# MB_RELAY.net
KiCad netlist of a schematic drawn in Altium Designer
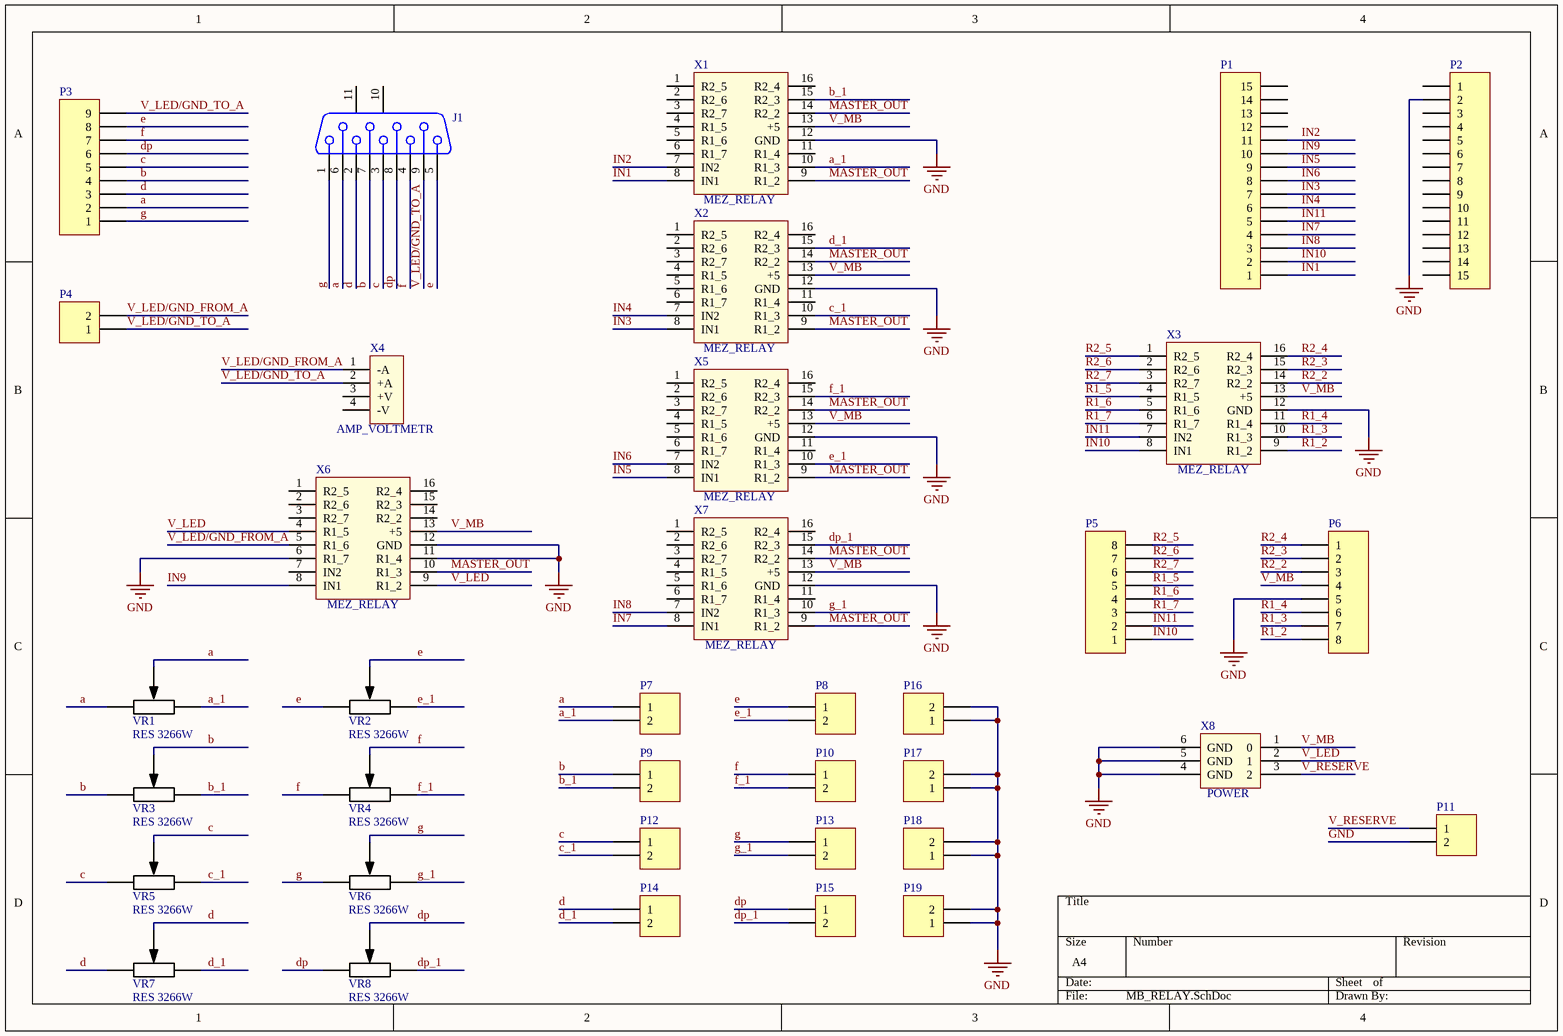
[diagram p0: MB_RELAY.SchDoc]

(export (version "E")
  (design (tool "Eeschema 10.0.6"))
  (components
    (comp (ref "J1")
      (value "D Connector 9")
      (footprint "DSUB1.385-2H9")
      (description "Receptacle Assembly, 9 Position, Right Angle")
      (fields (field (name "PUBLISHER") "Altium Limited"))
      (libsource (lib "Miscellaneous Connectors") (part "D Connector 9"))
    )
    (comp (ref "P1")
      (value "Header 15")
      (footprint "HDR1X15")
      (description "Header, 15-Pin")
      (fields (field (name "PUBLISHER") "Altium Limited"))
      (libsource (lib "Miscellaneous Connectors") (part "Header 15"))
    )
    (comp (ref "P2")
      (value "Header 15")
      (footprint "HDR1X15")
      (description "Header, 15-Pin")
      (fields (field (name "PUBLISHER") "Altium Limited"))
      (libsource (lib "") (part "Header 15_1"))
    )
    (comp (ref "P3")
      (value "Header 9")
      (footprint "HDR1X9")
      (description "Header, 9-Pin")
      (fields (field (name "PUBLISHER") "Altium Limited"))
      (libsource (lib "Miscellaneous Connectors") (part "Header 9"))
    )
    (comp (ref "P4")
      (value "Header 2")
      (footprint "HDR1X2")
      (description "Header, 2-Pin")
      (fields (field (name "PUBLISHER") "Altium Limited"))
      (libsource (lib "Miscellaneous Connectors") (part "Header 2"))
    )
    (comp (ref "P5")
      (value "Header 8")
      (footprint "HDR1X8")
      (description "Header, 8-Pin")
      (fields (field (name "PUBLISHER") "Altium Limited"))
      (libsource (lib "Miscellaneous Connectors") (part "Header 8"))
    )
    (comp (ref "P6")
      (value "Header 8")
      (footprint "HDR1X8")
      (description "Header, 8-Pin")
      (fields (field (name "PUBLISHER") "Altium Limited"))
      (libsource (lib "") (part "Header 8_1"))
    )
    (comp (ref "P7")
      (value "Header 2")
      (footprint "HDR1X2")
      (description "Header, 2-Pin")
      (fields (field (name "PUBLISHER") "Altium Limited"))
      (libsource (lib "") (part "Header 2_1"))
    )
    (comp (ref "P8")
      (value "Header 2")
      (footprint "HDR1X2")
      (description "Header, 2-Pin")
      (fields (field (name "PUBLISHER") "Altium Limited"))
      (libsource (lib "") (part "Header 2_1"))
    )
    (comp (ref "P9")
      (value "Header 2")
      (footprint "HDR1X2")
      (description "Header, 2-Pin")
      (fields (field (name "PUBLISHER") "Altium Limited"))
      (libsource (lib "") (part "Header 2_1"))
    )
    (comp (ref "P10")
      (value "Header 2")
      (footprint "HDR1X2")
      (description "Header, 2-Pin")
      (fields (field (name "PUBLISHER") "Altium Limited"))
      (libsource (lib "") (part "Header 2_1"))
    )
    (comp (ref "P11")
      (value "Header 2")
      (footprint "HDR1X2")
      (description "Header, 2-Pin")
      (fields (field (name "PUBLISHER") "Altium Limited"))
      (libsource (lib "") (part "Header 2_1"))
    )
    (comp (ref "P12")
      (value "Header 2")
      (footprint "HDR1X2")
      (description "Header, 2-Pin")
      (fields (field (name "PUBLISHER") "Altium Limited"))
      (libsource (lib "") (part "Header 2_1"))
    )
    (comp (ref "P13")
      (value "Header 2")
      (footprint "HDR1X2")
      (description "Header, 2-Pin")
      (fields (field (name "PUBLISHER") "Altium Limited"))
      (libsource (lib "") (part "Header 2_1"))
    )
    (comp (ref "P14")
      (value "Header 2")
      (footprint "HDR1X2")
      (description "Header, 2-Pin")
      (fields (field (name "PUBLISHER") "Altium Limited"))
      (libsource (lib "") (part "Header 2_1"))
    )
    (comp (ref "P15")
      (value "Header 2")
      (footprint "HDR1X2")
      (description "Header, 2-Pin")
      (fields (field (name "PUBLISHER") "Altium Limited"))
      (libsource (lib "") (part "Header 2_1"))
    )
    (comp (ref "P16")
      (value "Header 2")
      (footprint "HDR1X2")
      (description "Header, 2-Pin")
      (fields (field (name "PUBLISHER") "Altium Limited"))
      (libsource (lib "Miscellaneous Connectors") (part "Header 2"))
    )
    (comp (ref "P17")
      (value "Header 2")
      (footprint "HDR1X2")
      (description "Header, 2-Pin")
      (fields (field (name "PUBLISHER") "Altium Limited"))
      (libsource (lib "Miscellaneous Connectors") (part "Header 2"))
    )
    (comp (ref "P18")
      (value "Header 2")
      (footprint "HDR1X2")
      (description "Header, 2-Pin")
      (fields (field (name "PUBLISHER") "Altium Limited"))
      (libsource (lib "Miscellaneous Connectors") (part "Header 2"))
    )
    (comp (ref "P19")
      (value "Header 2")
      (footprint "HDR1X2")
      (description "Header, 2-Pin")
      (fields (field (name "PUBLISHER") "Altium Limited"))
      (libsource (lib "Miscellaneous Connectors") (part "Header 2"))
    )
    (comp (ref "VR1")
      (value "RES 3266W")
      (footprint "aab_Passive:RES 3266W")
      (libsource (lib "aab_Schlib") (part "RES 3266W"))
    )
    (comp (ref "VR2")
      (value "RES 3266W")
      (footprint "aab_Passive:RES 3266W")
      (libsource (lib "aab_Schlib") (part "RES 3266W"))
    )
    (comp (ref "VR3")
      (value "RES 3266W")
      (footprint "aab_Passive:RES 3266W")
      (libsource (lib "aab_Schlib") (part "RES 3266W"))
    )
    (comp (ref "VR4")
      (value "RES 3266W")
      (footprint "aab_Passive:RES 3266W")
      (libsource (lib "aab_Schlib") (part "RES 3266W"))
    )
    (comp (ref "VR5")
      (value "RES 3266W")
      (footprint "aab_Passive:RES 3266W")
      (libsource (lib "aab_Schlib") (part "RES 3266W"))
    )
    (comp (ref "VR6")
      (value "RES 3266W")
      (footprint "aab_Passive:RES 3266W")
      (libsource (lib "aab_Schlib") (part "RES 3266W"))
    )
    (comp (ref "VR7")
      (value "RES 3266W")
      (footprint "aab_Passive:RES 3266W")
      (libsource (lib "aab_Schlib") (part "RES 3266W"))
    )
    (comp (ref "VR8")
      (value "RES 3266W")
      (footprint "aab_Passive:RES 3266W")
      (libsource (lib "aab_Schlib") (part "RES 3266W"))
    )
    (comp (ref "X1")
      (value "MEZ_RELAY")
      (footprint "MEZ_RELAY")
      (libsource (lib "msp_SchLib") (part "MEZ_RELAY"))
    )
    (comp (ref "X2")
      (value "MEZ_RELAY")
      (footprint "MEZ_RELAY")
      (libsource (lib "msp_SchLib") (part "MEZ_RELAY"))
    )
    (comp (ref "X3")
      (value "MEZ_RELAY")
      (footprint "MEZ_RELAY")
      (libsource (lib "msp_SchLib") (part "MEZ_RELAY"))
    )
    (comp (ref "X4")
      (value "AMP_VOLTMETR")
      (footprint "vpl_Passive:AMP_VOLTMETER")
      (libsource (lib "msp_SchLib") (part "AMP_VOLTMETR"))
    )
    (comp (ref "X5")
      (value "MEZ_RELAY")
      (footprint "MEZ_RELAY")
      (libsource (lib "msp_SchLib") (part "MEZ_RELAY"))
    )
    (comp (ref "X6")
      (value "MEZ_RELAY")
      (footprint "MEZ_RELAY")
      (libsource (lib "msp_SchLib") (part "MEZ_RELAY"))
    )
    (comp (ref "X7")
      (value "MEZ_RELAY")
      (footprint "MEZ_RELAY")
      (libsource (lib "msp_SchLib") (part "MEZ_RELAY"))
    )
    (comp (ref "X8")
      (value "POWER")
      (footprint "vpl_Passive:POWER")
      (libsource (lib "msp_SchLib") (part "POWER"))
    )
  )
  (nets
    (net (code "1") (name "/IN1") (class "Default")
      (node (ref "P1") (pin "1") (pinfunction "1_1") (pintype "passive"))
      (node (ref "X1") (pin "8") (pinfunction "IN1_8") (pintype "passive"))
    )
    (net (code "2") (name "/IN2") (class "Default")
      (node (ref "P1") (pin "11") (pinfunction "11_11") (pintype "passive"))
      (node (ref "X1") (pin "7") (pinfunction "IN2_7") (pintype "passive"))
    )
    (net (code "3") (name "/IN3") (class "Default")
      (node (ref "P1") (pin "7") (pinfunction "7_7") (pintype "passive"))
      (node (ref "X2") (pin "8") (pinfunction "IN1_8") (pintype "passive"))
    )
    (net (code "4") (name "/IN4") (class "Default")
      (node (ref "P1") (pin "6") (pinfunction "6_6") (pintype "passive"))
      (node (ref "X2") (pin "7") (pinfunction "IN2_7") (pintype "passive"))
    )
    (net (code "5") (name "/IN5") (class "Default")
      (node (ref "P1") (pin "9") (pinfunction "9_9") (pintype "passive"))
      (node (ref "X5") (pin "8") (pinfunction "IN1_8") (pintype "passive"))
    )
    (net (code "6") (name "/IN6") (class "Default")
      (node (ref "P1") (pin "8") (pinfunction "8_8") (pintype "passive"))
      (node (ref "X5") (pin "7") (pinfunction "IN2_7") (pintype "passive"))
    )
    (net (code "7") (name "/IN7") (class "Default")
      (node (ref "P1") (pin "4") (pinfunction "4_4") (pintype "passive"))
      (node (ref "X7") (pin "8") (pinfunction "IN1_8") (pintype "passive"))
    )
    (net (code "8") (name "/IN8") (class "Default")
      (node (ref "P1") (pin "3") (pinfunction "3_3") (pintype "passive"))
      (node (ref "X7") (pin "7") (pinfunction "IN2_7") (pintype "passive"))
    )
    (net (code "9") (name "/IN9") (class "Default")
      (node (ref "P1") (pin "10") (pinfunction "10_10") (pintype "passive"))
      (node (ref "X6") (pin "8") (pinfunction "IN1_8") (pintype "passive"))
    )
    (net (code "10") (name "/IN10") (class "Default")
      (node (ref "P1") (pin "2") (pinfunction "2_2") (pintype "passive"))
      (node (ref "P5") (pin "1") (pinfunction "1_1") (pintype "passive"))
      (node (ref "X3") (pin "8") (pinfunction "IN1_8") (pintype "passive"))
    )
    (net (code "11") (name "/IN11") (class "Default")
      (node (ref "P1") (pin "5") (pinfunction "5_5") (pintype "passive"))
      (node (ref "P5") (pin "2") (pinfunction "2_2") (pintype "passive"))
      (node (ref "X3") (pin "7") (pinfunction "IN2_7") (pintype "passive"))
    )
    (net (code "12") (name "/MASTER_OUT") (class "Default")
      (node (ref "X1") (pin "14") (pinfunction "R2_2_14") (pintype "passive"))
      (node (ref "X1") (pin "9") (pinfunction "R1_2_9") (pintype "passive"))
      (node (ref "X2") (pin "14") (pinfunction "R2_2_14") (pintype "passive"))
      (node (ref "X2") (pin "9") (pinfunction "R1_2_9") (pintype "passive"))
      (node (ref "X5") (pin "14") (pinfunction "R2_2_14") (pintype "passive"))
      (node (ref "X5") (pin "9") (pinfunction "R1_2_9") (pintype "passive"))
      (node (ref "X6") (pin "10") (pinfunction "R1_3_10") (pintype "passive"))
      (node (ref "X7") (pin "14") (pinfunction "R2_2_14") (pintype "passive"))
      (node (ref "X7") (pin "9") (pinfunction "R1_2_9") (pintype "passive"))
    )
    (net (code "13") (name "/R1_2") (class "Default")
      (node (ref "P6") (pin "8") (pinfunction "8_8") (pintype "passive"))
      (node (ref "X3") (pin "9") (pinfunction "R1_2_9") (pintype "passive"))
    )
    (net (code "14") (name "/R1_3") (class "Default")
      (node (ref "P6") (pin "7") (pinfunction "7_7") (pintype "passive"))
      (node (ref "X3") (pin "10") (pinfunction "R1_3_10") (pintype "passive"))
    )
    (net (code "15") (name "/R1_4") (class "Default")
      (node (ref "P6") (pin "6") (pinfunction "6_6") (pintype "passive"))
      (node (ref "X3") (pin "11") (pinfunction "R1_4_11") (pintype "passive"))
    )
    (net (code "16") (name "/R1_5") (class "Default")
      (node (ref "P5") (pin "5") (pinfunction "5_5") (pintype "passive"))
      (node (ref "X3") (pin "4") (pinfunction "R1_5_4") (pintype "passive"))
    )
    (net (code "17") (name "/R1_6") (class "Default")
      (node (ref "P5") (pin "4") (pinfunction "4_4") (pintype "passive"))
      (node (ref "X3") (pin "5") (pinfunction "R1_6_5") (pintype "passive"))
    )
    (net (code "18") (name "/R1_7") (class "Default")
      (node (ref "P5") (pin "3") (pinfunction "3_3") (pintype "passive"))
      (node (ref "X3") (pin "6") (pinfunction "R1_7_6") (pintype "passive"))
    )
    (net (code "19") (name "/R2_2") (class "Default")
      (node (ref "P6") (pin "3") (pinfunction "3_3") (pintype "passive"))
      (node (ref "X3") (pin "14") (pinfunction "R2_2_14") (pintype "passive"))
    )
    (net (code "20") (name "/R2_3") (class "Default")
      (node (ref "P6") (pin "2") (pinfunction "2_2") (pintype "passive"))
      (node (ref "X3") (pin "15") (pinfunction "R2_3_15") (pintype "passive"))
    )
    (net (code "21") (name "/R2_4") (class "Default")
      (node (ref "P6") (pin "1") (pinfunction "1_1") (pintype "passive"))
      (node (ref "X3") (pin "16") (pinfunction "R2_4_16") (pintype "passive"))
    )
    (net (code "22") (name "/R2_5") (class "Default")
      (node (ref "P5") (pin "8") (pinfunction "8_8") (pintype "passive"))
      (node (ref "X3") (pin "1") (pinfunction "R2_5_1") (pintype "passive"))
    )
    (net (code "23") (name "/R2_6") (class "Default")
      (node (ref "P5") (pin "7") (pinfunction "7_7") (pintype "passive"))
      (node (ref "X3") (pin "2") (pinfunction "R2_6_2") (pintype "passive"))
    )
    (net (code "24") (name "/R2_7") (class "Default")
      (node (ref "P5") (pin "6") (pinfunction "6_6") (pintype "passive"))
      (node (ref "X3") (pin "3") (pinfunction "R2_7_3") (pintype "passive"))
    )
    (net (code "25") (name "/V_LED") (class "Default")
      (node (ref "X6") (pin "4") (pinfunction "R1_5_4") (pintype "passive"))
      (node (ref "X6") (pin "9") (pinfunction "R1_2_9") (pintype "passive"))
      (node (ref "X8") (pin "2") (pinfunction "1_2") (pintype "passive"))
    )
    (net (code "26") (name "/V_LED{slash}GND_FROM_A") (class "Default")
      (node (ref "P4") (pin "2") (pinfunction "2_2") (pintype "passive"))
      (node (ref "X4") (pin "1") (pinfunction "-A_1") (pintype "passive"))
      (node (ref "X6") (pin "5") (pinfunction "R1_6_5") (pintype "passive"))
    )
    (net (code "27") (name "/V_LED{slash}GND_TO_A") (class "Default")
      (node (ref "J1") (pin "9") (pinfunction "9_9") (pintype "passive"))
      (node (ref "P3") (pin "9") (pinfunction "9_9") (pintype "passive"))
      (node (ref "P4") (pin "1") (pinfunction "1_1") (pintype "passive"))
      (node (ref "X4") (pin "2") (pinfunction "+A_2") (pintype "passive"))
    )
    (net (code "28") (name "/V_MB") (class "Default")
      (node (ref "P6") (pin "4") (pinfunction "4_4") (pintype "passive"))
      (node (ref "X1") (pin "13") (pinfunction "+5_13") (pintype "passive"))
      (node (ref "X2") (pin "13") (pinfunction "+5_13") (pintype "passive"))
      (node (ref "X3") (pin "13") (pinfunction "+5_13") (pintype "passive"))
      (node (ref "X5") (pin "13") (pinfunction "+5_13") (pintype "passive"))
      (node (ref "X6") (pin "13") (pinfunction "+5_13") (pintype "passive"))
      (node (ref "X7") (pin "13") (pinfunction "+5_13") (pintype "passive"))
      (node (ref "X8") (pin "1") (pinfunction "0_1") (pintype "passive"))
    )
    (net (code "29") (name "/V_RESERVE") (class "Default")
      (node (ref "P11") (pin "1") (pinfunction "1_1") (pintype "passive"))
      (node (ref "X8") (pin "3") (pinfunction "2_3") (pintype "passive"))
    )
    (net (code "30") (name "/a") (class "Default")
      (node (ref "J1") (pin "6") (pinfunction "6_6") (pintype "passive"))
      (node (ref "P3") (pin "2") (pinfunction "2_2") (pintype "passive"))
      (node (ref "P7") (pin "1") (pinfunction "1_1") (pintype "passive"))
      (node (ref "VR1") (pin "1") (pinfunction "1_1") (pintype "passive"))
      (node (ref "VR1") (pin "2") (pinfunction "2_2") (pintype "passive"))
    )
    (net (code "31") (name "/a_1") (class "Default")
      (node (ref "P7") (pin "2") (pinfunction "2_2") (pintype "passive"))
      (node (ref "VR1") (pin "3") (pinfunction "3_3") (pintype "passive"))
      (node (ref "X1") (pin "10") (pinfunction "R1_3_10") (pintype "passive"))
    )
    (net (code "32") (name "/b") (class "Default")
      (node (ref "J1") (pin "7") (pinfunction "7_7") (pintype "passive"))
      (node (ref "P3") (pin "4") (pinfunction "4_4") (pintype "passive"))
      (node (ref "P9") (pin "1") (pinfunction "1_1") (pintype "passive"))
      (node (ref "VR3") (pin "1") (pinfunction "1_1") (pintype "passive"))
      (node (ref "VR3") (pin "2") (pinfunction "2_2") (pintype "passive"))
    )
    (net (code "33") (name "/b_1") (class "Default")
      (node (ref "P9") (pin "2") (pinfunction "2_2") (pintype "passive"))
      (node (ref "VR3") (pin "3") (pinfunction "3_3") (pintype "passive"))
      (node (ref "X1") (pin "15") (pinfunction "R2_3_15") (pintype "passive"))
    )
    (net (code "34") (name "/c") (class "Default")
      (node (ref "J1") (pin "3") (pinfunction "3_3") (pintype "passive"))
      (node (ref "P12") (pin "1") (pinfunction "1_1") (pintype "passive"))
      (node (ref "P3") (pin "5") (pinfunction "5_5") (pintype "passive"))
      (node (ref "VR5") (pin "1") (pinfunction "1_1") (pintype "passive"))
      (node (ref "VR5") (pin "2") (pinfunction "2_2") (pintype "passive"))
    )
    (net (code "35") (name "/c_1") (class "Default")
      (node (ref "P12") (pin "2") (pinfunction "2_2") (pintype "passive"))
      (node (ref "VR5") (pin "3") (pinfunction "3_3") (pintype "passive"))
      (node (ref "X2") (pin "10") (pinfunction "R1_3_10") (pintype "passive"))
    )
    (net (code "36") (name "/d") (class "Default")
      (node (ref "J1") (pin "2") (pinfunction "2_2") (pintype "passive"))
      (node (ref "P14") (pin "1") (pinfunction "1_1") (pintype "passive"))
      (node (ref "P3") (pin "3") (pinfunction "3_3") (pintype "passive"))
      (node (ref "VR7") (pin "1") (pinfunction "1_1") (pintype "passive"))
      (node (ref "VR7") (pin "2") (pinfunction "2_2") (pintype "passive"))
    )
    (net (code "37") (name "/d_1") (class "Default")
      (node (ref "P14") (pin "2") (pinfunction "2_2") (pintype "passive"))
      (node (ref "VR7") (pin "3") (pinfunction "3_3") (pintype "passive"))
      (node (ref "X2") (pin "15") (pinfunction "R2_3_15") (pintype "passive"))
    )
    (net (code "38") (name "/dp") (class "Default")
      (node (ref "J1") (pin "8") (pinfunction "8_8") (pintype "passive"))
      (node (ref "P15") (pin "1") (pinfunction "1_1") (pintype "passive"))
      (node (ref "P3") (pin "6") (pinfunction "6_6") (pintype "passive"))
      (node (ref "VR8") (pin "1") (pinfunction "1_1") (pintype "passive"))
      (node (ref "VR8") (pin "2") (pinfunction "2_2") (pintype "passive"))
    )
    (net (code "39") (name "/dp_1") (class "Default")
      (node (ref "P15") (pin "2") (pinfunction "2_2") (pintype "passive"))
      (node (ref "VR8") (pin "3") (pinfunction "3_3") (pintype "passive"))
      (node (ref "X7") (pin "15") (pinfunction "R2_3_15") (pintype "passive"))
    )
    (net (code "40") (name "/e") (class "Default")
      (node (ref "J1") (pin "5") (pinfunction "5_5") (pintype "passive"))
      (node (ref "P3") (pin "8") (pinfunction "8_8") (pintype "passive"))
      (node (ref "P8") (pin "1") (pinfunction "1_1") (pintype "passive"))
      (node (ref "VR2") (pin "1") (pinfunction "1_1") (pintype "passive"))
      (node (ref "VR2") (pin "2") (pinfunction "2_2") (pintype "passive"))
    )
    (net (code "41") (name "/e_1") (class "Default")
      (node (ref "P8") (pin "2") (pinfunction "2_2") (pintype "passive"))
      (node (ref "VR2") (pin "3") (pinfunction "3_3") (pintype "passive"))
      (node (ref "X5") (pin "10") (pinfunction "R1_3_10") (pintype "passive"))
    )
    (net (code "42") (name "/f") (class "Default")
      (node (ref "J1") (pin "4") (pinfunction "4_4") (pintype "passive"))
      (node (ref "P10") (pin "1") (pinfunction "1_1") (pintype "passive"))
      (node (ref "P3") (pin "7") (pinfunction "7_7") (pintype "passive"))
      (node (ref "VR4") (pin "1") (pinfunction "1_1") (pintype "passive"))
      (node (ref "VR4") (pin "2") (pinfunction "2_2") (pintype "passive"))
    )
    (net (code "43") (name "/f_1") (class "Default")
      (node (ref "P10") (pin "2") (pinfunction "2_2") (pintype "passive"))
      (node (ref "VR4") (pin "3") (pinfunction "3_3") (pintype "passive"))
      (node (ref "X5") (pin "15") (pinfunction "R2_3_15") (pintype "passive"))
    )
    (net (code "44") (name "/g") (class "Default")
      (node (ref "J1") (pin "1") (pinfunction "1_1") (pintype "passive"))
      (node (ref "P13") (pin "1") (pinfunction "1_1") (pintype "passive"))
      (node (ref "P3") (pin "1") (pinfunction "1_1") (pintype "passive"))
      (node (ref "VR6") (pin "1") (pinfunction "1_1") (pintype "passive"))
      (node (ref "VR6") (pin "2") (pinfunction "2_2") (pintype "passive"))
    )
    (net (code "45") (name "/g_1") (class "Default")
      (node (ref "P13") (pin "2") (pinfunction "2_2") (pintype "passive"))
      (node (ref "VR6") (pin "3") (pinfunction "3_3") (pintype "passive"))
      (node (ref "X7") (pin "10") (pinfunction "R1_3_10") (pintype "passive"))
    )
    (net (code "46") (name "GND") (class "Default")
      (node (ref "P11") (pin "2") (pinfunction "2_2") (pintype "passive"))
      (node (ref "P16") (pin "1") (pinfunction "1_1") (pintype "passive"))
      (node (ref "P16") (pin "2") (pinfunction "2_2") (pintype "passive"))
      (node (ref "P17") (pin "1") (pinfunction "1_1") (pintype "passive"))
      (node (ref "P17") (pin "2") (pinfunction "2_2") (pintype "passive"))
      (node (ref "P18") (pin "1") (pinfunction "1_1") (pintype "passive"))
      (node (ref "P18") (pin "2") (pinfunction "2_2") (pintype "passive"))
      (node (ref "P19") (pin "1") (pinfunction "1_1") (pintype "passive"))
      (node (ref "P19") (pin "2") (pinfunction "2_2") (pintype "passive"))
      (node (ref "P2") (pin "2") (pinfunction "2_2") (pintype "passive"))
      (node (ref "P6") (pin "5") (pinfunction "5_5") (pintype "passive"))
      (node (ref "X1") (pin "12") (pinfunction "GND_12") (pintype "passive"))
      (node (ref "X2") (pin "12") (pinfunction "GND_12") (pintype "passive"))
      (node (ref "X3") (pin "12") (pinfunction "GND_12") (pintype "passive"))
      (node (ref "X5") (pin "12") (pinfunction "GND_12") (pintype "passive"))
      (node (ref "X6") (pin "11") (pinfunction "R1_4_11") (pintype "passive"))
      (node (ref "X6") (pin "12") (pinfunction "GND_12") (pintype "passive"))
      (node (ref "X6") (pin "6") (pinfunction "R1_7_6") (pintype "passive"))
      (node (ref "X7") (pin "12") (pinfunction "GND_12") (pintype "passive"))
      (node (ref "X8") (pin "4") (pinfunction "GND_4") (pintype "passive"))
      (node (ref "X8") (pin "5") (pinfunction "GND_5") (pintype "passive"))
      (node (ref "X8") (pin "6") (pinfunction "GND_6") (pintype "passive"))
    )
    (net (code "47") (name "unconnected-(J1-MH1-Pad10)") (class "Default")
      (node (ref "J1") (pin "10") (pinfunction "MH1_10") (pintype "passive"))
    )
    (net (code "48") (name "unconnected-(J1-MH2-Pad11)") (class "Default")
      (node (ref "J1") (pin "11") (pinfunction "MH2_11") (pintype "passive"))
    )
    (net (code "49") (name "unconnected-(P1-Pad12)") (class "Default")
      (node (ref "P1") (pin "12") (pinfunction "12_12") (pintype "passive"))
    )
    (net (code "50") (name "unconnected-(P1-Pad13)") (class "Default")
      (node (ref "P1") (pin "13") (pinfunction "13_13") (pintype "passive"))
    )
    (net (code "51") (name "unconnected-(P1-Pad14)") (class "Default")
      (node (ref "P1") (pin "14") (pinfunction "14_14") (pintype "passive"))
    )
    (net (code "52") (name "unconnected-(P1-Pad15)") (class "Default")
      (node (ref "P1") (pin "15") (pinfunction "15_15") (pintype "passive"))
    )
    (net (code "53") (name "unconnected-(P2-Pad1)") (class "Default")
      (node (ref "P2") (pin "1") (pinfunction "1_1") (pintype "passive"))
    )
    (net (code "54") (name "unconnected-(P2-Pad3)") (class "Default")
      (node (ref "P2") (pin "3") (pinfunction "3_3") (pintype "passive"))
    )
    (net (code "55") (name "unconnected-(P2-Pad4)") (class "Default")
      (node (ref "P2") (pin "4") (pinfunction "4_4") (pintype "passive"))
    )
    (net (code "56") (name "unconnected-(P2-Pad5)") (class "Default")
      (node (ref "P2") (pin "5") (pinfunction "5_5") (pintype "passive"))
    )
    (net (code "57") (name "unconnected-(P2-Pad6)") (class "Default")
      (node (ref "P2") (pin "6") (pinfunction "6_6") (pintype "passive"))
    )
    (net (code "58") (name "unconnected-(P2-Pad7)") (class "Default")
      (node (ref "P2") (pin "7") (pinfunction "7_7") (pintype "passive"))
    )
    (net (code "59") (name "unconnected-(P2-Pad8)") (class "Default")
      (node (ref "P2") (pin "8") (pinfunction "8_8") (pintype "passive"))
    )
    (net (code "60") (name "unconnected-(P2-Pad9)") (class "Default")
      (node (ref "P2") (pin "9") (pinfunction "9_9") (pintype "passive"))
    )
    (net (code "61") (name "unconnected-(P2-Pad10)") (class "Default")
      (node (ref "P2") (pin "10") (pinfunction "10_10") (pintype "passive"))
    )
    (net (code "62") (name "unconnected-(P2-Pad11)") (class "Default")
      (node (ref "P2") (pin "11") (pinfunction "11_11") (pintype "passive"))
    )
    (net (code "63") (name "unconnected-(P2-Pad12)") (class "Default")
      (node (ref "P2") (pin "12") (pinfunction "12_12") (pintype "passive"))
    )
    (net (code "64") (name "unconnected-(P2-Pad13)") (class "Default")
      (node (ref "P2") (pin "13") (pinfunction "13_13") (pintype "passive"))
    )
    (net (code "65") (name "unconnected-(P2-Pad14)") (class "Default")
      (node (ref "P2") (pin "14") (pinfunction "14_14") (pintype "passive"))
    )
    (net (code "66") (name "unconnected-(P2-Pad15)") (class "Default")
      (node (ref "P2") (pin "15") (pinfunction "15_15") (pintype "passive"))
    )
    (net (code "67") (name "unconnected-(X1-R1_4-Pad11)") (class "Default")
      (node (ref "X1") (pin "11") (pinfunction "R1_4_11") (pintype "passive"))
    )
    (net (code "68") (name "unconnected-(X1-R1_5-Pad4)") (class "Default")
      (node (ref "X1") (pin "4") (pinfunction "R1_5_4") (pintype "passive"))
    )
    (net (code "69") (name "unconnected-(X1-R1_6-Pad5)") (class "Default")
      (node (ref "X1") (pin "5") (pinfunction "R1_6_5") (pintype "passive"))
    )
    (net (code "70") (name "unconnected-(X1-R1_7-Pad6)") (class "Default")
      (node (ref "X1") (pin "6") (pinfunction "R1_7_6") (pintype "passive"))
    )
    (net (code "71") (name "unconnected-(X1-R2_4-Pad16)") (class "Default")
      (node (ref "X1") (pin "16") (pinfunction "R2_4_16") (pintype "passive"))
    )
    (net (code "72") (name "unconnected-(X1-R2_5-Pad1)") (class "Default")
      (node (ref "X1") (pin "1") (pinfunction "R2_5_1") (pintype "passive"))
    )
    (net (code "73") (name "unconnected-(X1-R2_6-Pad2)") (class "Default")
      (node (ref "X1") (pin "2") (pinfunction "R2_6_2") (pintype "passive"))
    )
    (net (code "74") (name "unconnected-(X1-R2_7-Pad3)") (class "Default")
      (node (ref "X1") (pin "3") (pinfunction "R2_7_3") (pintype "passive"))
    )
    (net (code "75") (name "unconnected-(X2-R1_4-Pad11)") (class "Default")
      (node (ref "X2") (pin "11") (pinfunction "R1_4_11") (pintype "passive"))
    )
    (net (code "76") (name "unconnected-(X2-R1_5-Pad4)") (class "Default")
      (node (ref "X2") (pin "4") (pinfunction "R1_5_4") (pintype "passive"))
    )
    (net (code "77") (name "unconnected-(X2-R1_6-Pad5)") (class "Default")
      (node (ref "X2") (pin "5") (pinfunction "R1_6_5") (pintype "passive"))
    )
    (net (code "78") (name "unconnected-(X2-R1_7-Pad6)") (class "Default")
      (node (ref "X2") (pin "6") (pinfunction "R1_7_6") (pintype "passive"))
    )
    (net (code "79") (name "unconnected-(X2-R2_4-Pad16)") (class "Default")
      (node (ref "X2") (pin "16") (pinfunction "R2_4_16") (pintype "passive"))
    )
    (net (code "80") (name "unconnected-(X2-R2_5-Pad1)") (class "Default")
      (node (ref "X2") (pin "1") (pinfunction "R2_5_1") (pintype "passive"))
    )
    (net (code "81") (name "unconnected-(X2-R2_6-Pad2)") (class "Default")
      (node (ref "X2") (pin "2") (pinfunction "R2_6_2") (pintype "passive"))
    )
    (net (code "82") (name "unconnected-(X2-R2_7-Pad3)") (class "Default")
      (node (ref "X2") (pin "3") (pinfunction "R2_7_3") (pintype "passive"))
    )
    (net (code "83") (name "unconnected-(X4-+V-Pad3)") (class "Default")
      (node (ref "X4") (pin "3") (pinfunction "+V_3") (pintype "passive"))
    )
    (net (code "84") (name "unconnected-(X4--V-Pad4)") (class "Default")
      (node (ref "X4") (pin "4") (pinfunction "-V_4") (pintype "passive"))
    )
    (net (code "85") (name "unconnected-(X5-R1_4-Pad11)") (class "Default")
      (node (ref "X5") (pin "11") (pinfunction "R1_4_11") (pintype "passive"))
    )
    (net (code "86") (name "unconnected-(X5-R1_5-Pad4)") (class "Default")
      (node (ref "X5") (pin "4") (pinfunction "R1_5_4") (pintype "passive"))
    )
    (net (code "87") (name "unconnected-(X5-R1_6-Pad5)") (class "Default")
      (node (ref "X5") (pin "5") (pinfunction "R1_6_5") (pintype "passive"))
    )
    (net (code "88") (name "unconnected-(X5-R1_7-Pad6)") (class "Default")
      (node (ref "X5") (pin "6") (pinfunction "R1_7_6") (pintype "passive"))
    )
    (net (code "89") (name "unconnected-(X5-R2_4-Pad16)") (class "Default")
      (node (ref "X5") (pin "16") (pinfunction "R2_4_16") (pintype "passive"))
    )
    (net (code "90") (name "unconnected-(X5-R2_5-Pad1)") (class "Default")
      (node (ref "X5") (pin "1") (pinfunction "R2_5_1") (pintype "passive"))
    )
    (net (code "91") (name "unconnected-(X5-R2_6-Pad2)") (class "Default")
      (node (ref "X5") (pin "2") (pinfunction "R2_6_2") (pintype "passive"))
    )
    (net (code "92") (name "unconnected-(X5-R2_7-Pad3)") (class "Default")
      (node (ref "X5") (pin "3") (pinfunction "R2_7_3") (pintype "passive"))
    )
    (net (code "93") (name "unconnected-(X6-IN2-Pad7)") (class "Default")
      (node (ref "X6") (pin "7") (pinfunction "IN2_7") (pintype "passive"))
    )
    (net (code "94") (name "unconnected-(X6-R2_2-Pad14)") (class "Default")
      (node (ref "X6") (pin "14") (pinfunction "R2_2_14") (pintype "passive"))
    )
    (net (code "95") (name "unconnected-(X6-R2_3-Pad15)") (class "Default")
      (node (ref "X6") (pin "15") (pinfunction "R2_3_15") (pintype "passive"))
    )
    (net (code "96") (name "unconnected-(X6-R2_4-Pad16)") (class "Default")
      (node (ref "X6") (pin "16") (pinfunction "R2_4_16") (pintype "passive"))
    )
    (net (code "97") (name "unconnected-(X6-R2_5-Pad1)") (class "Default")
      (node (ref "X6") (pin "1") (pinfunction "R2_5_1") (pintype "passive"))
    )
    (net (code "98") (name "unconnected-(X6-R2_6-Pad2)") (class "Default")
      (node (ref "X6") (pin "2") (pinfunction "R2_6_2") (pintype "passive"))
    )
    (net (code "99") (name "unconnected-(X6-R2_7-Pad3)") (class "Default")
      (node (ref "X6") (pin "3") (pinfunction "R2_7_3") (pintype "passive"))
    )
    (net (code "100") (name "unconnected-(X7-R1_4-Pad11)") (class "Default")
      (node (ref "X7") (pin "11") (pinfunction "R1_4_11") (pintype "passive"))
    )
    (net (code "101") (name "unconnected-(X7-R1_5-Pad4)") (class "Default")
      (node (ref "X7") (pin "4") (pinfunction "R1_5_4") (pintype "passive"))
    )
    (net (code "102") (name "unconnected-(X7-R1_6-Pad5)") (class "Default")
      (node (ref "X7") (pin "5") (pinfunction "R1_6_5") (pintype "passive"))
    )
    (net (code "103") (name "unconnected-(X7-R1_7-Pad6)") (class "Default")
      (node (ref "X7") (pin "6") (pinfunction "R1_7_6") (pintype "passive"))
    )
    (net (code "104") (name "unconnected-(X7-R2_4-Pad16)") (class "Default")
      (node (ref "X7") (pin "16") (pinfunction "R2_4_16") (pintype "passive"))
    )
    (net (code "105") (name "unconnected-(X7-R2_5-Pad1)") (class "Default")
      (node (ref "X7") (pin "1") (pinfunction "R2_5_1") (pintype "passive"))
    )
    (net (code "106") (name "unconnected-(X7-R2_6-Pad2)") (class "Default")
      (node (ref "X7") (pin "2") (pinfunction "R2_6_2") (pintype "passive"))
    )
    (net (code "107") (name "unconnected-(X7-R2_7-Pad3)") (class "Default")
      (node (ref "X7") (pin "3") (pinfunction "R2_7_3") (pintype "passive"))
    )
  )
)
